# LPCB279_-_HBRIDGE.net
KiCad netlist of a schematic drawn in Altium Designer
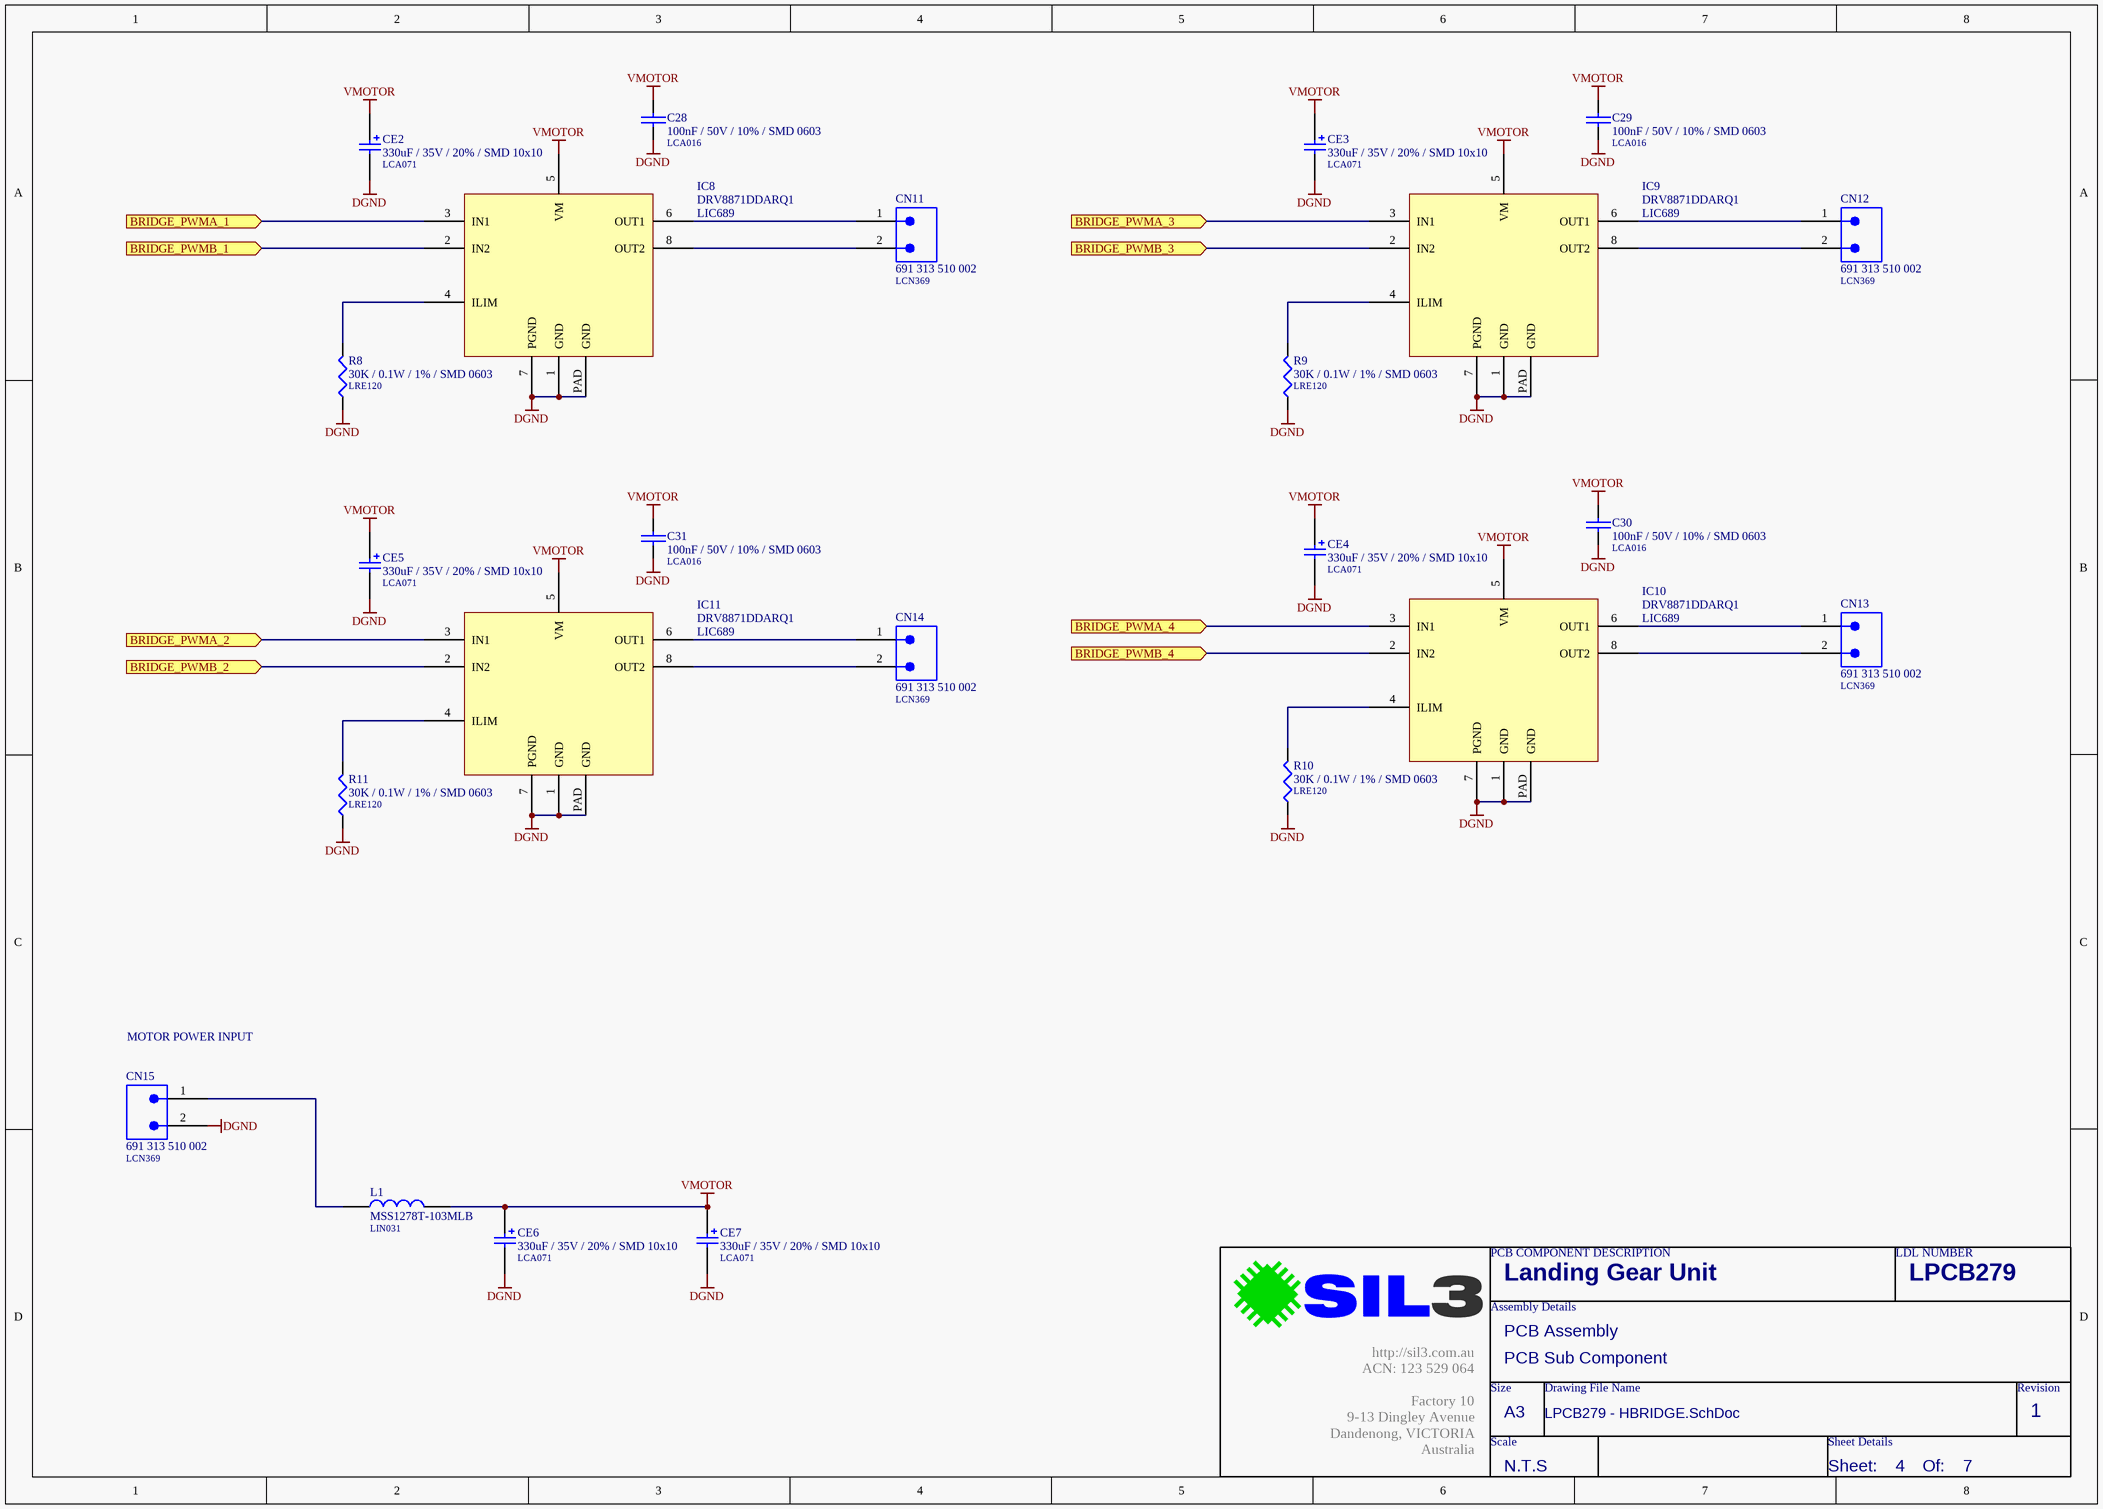
[diagram p0: LPCB279 - HBRIDGE.SchDoc]

(export (version "E")
  (design (tool "Eeschema 10.0.6"))
  (components
    (comp (ref "C28")
      (value "100nF / 50V / 10% / SMD 0603")
      (footprint "LFP011__CC1608-0603-IPC7351_B")
      (description "Capacitor, Ceramic Chip, 100nF (0.1uF), 50V, 5%, SMD 0603 [LCA016]")
      (fields (field (name "LDL_NUMBER") "LCA016"))
      (libsource (lib "LDL_Capacitors") (part "100nF / 50V / 10% / SMD 0603"))
    )
    (comp (ref "C29")
      (value "100nF / 50V / 10% / SMD 0603")
      (footprint "LFP011__CC1608-0603-IPC7351_B")
      (description "Capacitor, Ceramic Chip, 100nF (0.1uF), 50V, 5%, SMD 0603 [LCA016]")
      (fields (field (name "LDL_NUMBER") "LCA016"))
      (libsource (lib "LDL_Capacitors") (part "100nF / 50V / 10% / SMD 0603"))
    )
    (comp (ref "C30")
      (value "100nF / 50V / 10% / SMD 0603")
      (footprint "LFP011__CC1608-0603-IPC7351_B")
      (description "Capacitor, Ceramic Chip, 100nF (0.1uF), 50V, 5%, SMD 0603 [LCA016]")
      (fields (field (name "LDL_NUMBER") "LCA016"))
      (libsource (lib "LDL_Capacitors") (part "100nF / 50V / 10% / SMD 0603"))
    )
    (comp (ref "C31")
      (value "100nF / 50V / 10% / SMD 0603")
      (footprint "LFP011__CC1608-0603-IPC7351_B")
      (description "Capacitor, Ceramic Chip, 100nF (0.1uF), 50V, 5%, SMD 0603 [LCA016]")
      (fields (field (name "LDL_NUMBER") "LCA016"))
      (libsource (lib "LDL_Capacitors") (part "100nF / 50V / 10% / SMD 0603"))
    )
    (comp (ref "CE2")
      (value "330uF / 35V / 20% / SMD 10x10")
      (footprint "LFP041__NICHICON_WT_10X10")
      (description "Capacitor, Aluminum Electrolytic, 330uF, 35V, 20%, SMD (10mm x 10mm) [LCA071]")
      (fields (field (name "LDL_NUMBER") "LCA071"))
      (libsource (lib "LDL_Capacitors") (part "330uF / 35V / 20% / SMD 10x10"))
    )
    (comp (ref "CE3")
      (value "330uF / 35V / 20% / SMD 10x10")
      (footprint "LFP041__NICHICON_WT_10X10")
      (description "Capacitor, Aluminum Electrolytic, 330uF, 35V, 20%, SMD (10mm x 10mm) [LCA071]")
      (fields (field (name "LDL_NUMBER") "LCA071"))
      (libsource (lib "LDL_Capacitors") (part "330uF / 35V / 20% / SMD 10x10"))
    )
    (comp (ref "CE4")
      (value "330uF / 35V / 20% / SMD 10x10")
      (footprint "LFP041__NICHICON_WT_10X10")
      (description "Capacitor, Aluminum Electrolytic, 330uF, 35V, 20%, SMD (10mm x 10mm) [LCA071]")
      (fields (field (name "LDL_NUMBER") "LCA071"))
      (libsource (lib "LDL_Capacitors") (part "330uF / 35V / 20% / SMD 10x10"))
    )
    (comp (ref "CE5")
      (value "330uF / 35V / 20% / SMD 10x10")
      (footprint "LFP041__NICHICON_WT_10X10")
      (description "Capacitor, Aluminum Electrolytic, 330uF, 35V, 20%, SMD (10mm x 10mm) [LCA071]")
      (fields (field (name "LDL_NUMBER") "LCA071"))
      (libsource (lib "LDL_Capacitors") (part "330uF / 35V / 20% / SMD 10x10"))
    )
    (comp (ref "CE6")
      (value "330uF / 35V / 20% / SMD 10x10")
      (footprint "LFP041__NICHICON_WT_10X10")
      (description "Capacitor, Aluminum Electrolytic, 330uF, 35V, 20%, SMD (10mm x 10mm) [LCA071]")
      (fields (field (name "LDL_NUMBER") "LCA071"))
      (libsource (lib "LDL_Capacitors") (part "330uF / 35V / 20% / SMD 10x10"))
    )
    (comp (ref "CE7")
      (value "330uF / 35V / 20% / SMD 10x10")
      (footprint "LFP041__NICHICON_WT_10X10")
      (description "Capacitor, Aluminum Electrolytic, 330uF, 35V, 20%, SMD (10mm x 10mm) [LCA071]")
      (fields (field (name "LDL_NUMBER") "LCA071"))
      (libsource (lib "LDL_Capacitors") (part "330uF / 35V / 20% / SMD 10x10"))
    )
    (comp (ref "CN11")
      (value "691 313 510 002")
      (footprint "691 313 510 002")
      (description "Connector, Pluggable Terminal Block, 5.08mm, 2 Way, PTH")
      (fields (field (name "LDL_NUMBER") "LCN369"))
      (libsource (lib "LDL_Connectors") (part "691 313 510 002"))
    )
    (comp (ref "CN12")
      (value "691 313 510 002")
      (footprint "691 313 510 002")
      (description "Connector, Pluggable Terminal Block, 5.08mm, 2 Way, PTH")
      (fields (field (name "LDL_NUMBER") "LCN369"))
      (libsource (lib "LDL_Connectors") (part "691 313 510 002"))
    )
    (comp (ref "CN13")
      (value "691 313 510 002")
      (footprint "691 313 510 002")
      (description "Connector, Pluggable Terminal Block, 5.08mm, 2 Way, PTH")
      (fields (field (name "LDL_NUMBER") "LCN369"))
      (libsource (lib "LDL_Connectors") (part "691 313 510 002"))
    )
    (comp (ref "CN14")
      (value "691 313 510 002")
      (footprint "691 313 510 002")
      (description "Connector, Pluggable Terminal Block, 5.08mm, 2 Way, PTH")
      (fields (field (name "LDL_NUMBER") "LCN369"))
      (libsource (lib "LDL_Connectors") (part "691 313 510 002"))
    )
    (comp (ref "CN15")
      (value "691 313 510 002")
      (footprint "691 313 510 002")
      (description "Connector, Pluggable Terminal Block, 5.08mm, 2 Way, PTH")
      (fields (field (name "LDL_NUMBER") "LCN369"))
      (libsource (lib "LDL_Connectors") (part "691 313 510 002"))
    )
    (comp (ref "IC8")
      (value "DRV8871DDARQ1")
      (footprint "LFP158__DDA_R-PDSO-G8")
      (description "IC, DC Motor Driver, 3.6A, SMD [LIC689]")
      (fields (field (name "LDL_NUMBER") "LIC689"))
      (libsource (lib "LDL_Semiconductors") (part "DRV8871DDARQ1"))
    )
    (comp (ref "IC9")
      (value "DRV8871DDARQ1")
      (footprint "LFP158__DDA_R-PDSO-G8")
      (description "IC, DC Motor Driver, 3.6A, SMD [LIC689]")
      (fields (field (name "LDL_NUMBER") "LIC689"))
      (libsource (lib "LDL_Semiconductors") (part "DRV8871DDARQ1"))
    )
    (comp (ref "IC10")
      (value "DRV8871DDARQ1")
      (footprint "LFP158__DDA_R-PDSO-G8")
      (description "IC, DC Motor Driver, 3.6A, SMD [LIC689]")
      (fields (field (name "LDL_NUMBER") "LIC689"))
      (libsource (lib "LDL_Semiconductors") (part "DRV8871DDARQ1"))
    )
    (comp (ref "IC11")
      (value "DRV8871DDARQ1")
      (footprint "LFP158__DDA_R-PDSO-G8")
      (description "IC, DC Motor Driver, 3.6A, SMD [LIC689]")
      (fields (field (name "LDL_NUMBER") "LIC689"))
      (libsource (lib "LDL_Semiconductors") (part "DRV8871DDARQ1"))
    )
    (comp (ref "L1")
      (value "MSS1278T-103MLB")
      (footprint "LFP037__MSS1278T")
      (description "Inductor, 10uH, 20%, 5.7A, SMD [LIN031]")
      (fields (field (name "LDL_NUMBER") "LIN031"))
      (libsource (lib "LDL_Inductors") (part "MSS1278T-103MLB"))
    )
    (comp (ref "R8")
      (value "30K / 0.1W / 1% / SMD 0603")
      (footprint "LFP020__CR1608-0603-IPC7351_B")
      (description "Resistor, Ceramic Chip, 30K, 0.1W, 1%, SMD 0603 [LRE120]")
      (fields (field (name "LDL_NUMBER") "LRE120"))
      (libsource (lib "LDL_Resistors") (part "30K / 0.1W / 1% / SMD 0603"))
    )
    (comp (ref "R9")
      (value "30K / 0.1W / 1% / SMD 0603")
      (footprint "LFP020__CR1608-0603-IPC7351_B")
      (description "Resistor, Ceramic Chip, 30K, 0.1W, 1%, SMD 0603 [LRE120]")
      (fields (field (name "LDL_NUMBER") "LRE120"))
      (libsource (lib "LDL_Resistors") (part "30K / 0.1W / 1% / SMD 0603"))
    )
    (comp (ref "R10")
      (value "30K / 0.1W / 1% / SMD 0603")
      (footprint "LFP020__CR1608-0603-IPC7351_B")
      (description "Resistor, Ceramic Chip, 30K, 0.1W, 1%, SMD 0603 [LRE120]")
      (fields (field (name "LDL_NUMBER") "LRE120"))
      (libsource (lib "LDL_Resistors") (part "30K / 0.1W / 1% / SMD 0603"))
    )
    (comp (ref "R11")
      (value "30K / 0.1W / 1% / SMD 0603")
      (footprint "LFP020__CR1608-0603-IPC7351_B")
      (description "Resistor, Ceramic Chip, 30K, 0.1W, 1%, SMD 0603 [LRE120]")
      (fields (field (name "LDL_NUMBER") "LRE120"))
      (libsource (lib "LDL_Resistors") (part "30K / 0.1W / 1% / SMD 0603"))
    )
  )
  (nets
    (net (code "1") (name "/BRIDGE_PWMA_1") (class "Default")
      (node (ref "IC8") (pin "3") (pinfunction "IN1_3") (pintype "passive"))
    )
    (net (code "2") (name "/BRIDGE_PWMA_2") (class "Default")
      (node (ref "IC11") (pin "3") (pinfunction "IN1_3") (pintype "passive"))
    )
    (net (code "3") (name "/BRIDGE_PWMA_3") (class "Default")
      (node (ref "IC9") (pin "3") (pinfunction "IN1_3") (pintype "passive"))
    )
    (net (code "4") (name "/BRIDGE_PWMA_4") (class "Default")
      (node (ref "IC10") (pin "3") (pinfunction "IN1_3") (pintype "passive"))
    )
    (net (code "5") (name "/BRIDGE_PWMB_1") (class "Default")
      (node (ref "IC8") (pin "2") (pinfunction "IN2_2") (pintype "passive"))
    )
    (net (code "6") (name "/BRIDGE_PWMB_2") (class "Default")
      (node (ref "IC11") (pin "2") (pinfunction "IN2_2") (pintype "passive"))
    )
    (net (code "7") (name "/BRIDGE_PWMB_3") (class "Default")
      (node (ref "IC9") (pin "2") (pinfunction "IN2_2") (pintype "passive"))
    )
    (net (code "8") (name "/BRIDGE_PWMB_4") (class "Default")
      (node (ref "IC10") (pin "2") (pinfunction "IN2_2") (pintype "passive"))
    )
    (net (code "9") (name "DGND") (class "Default")
      (node (ref "C28") (pin "2") (pintype "passive"))
      (node (ref "C29") (pin "2") (pintype "passive"))
      (node (ref "C30") (pin "2") (pintype "passive"))
      (node (ref "C31") (pin "2") (pintype "passive"))
      (node (ref "CE2") (pin "2") (pinfunction "2_2") (pintype "passive"))
      (node (ref "CE3") (pin "2") (pinfunction "2_2") (pintype "passive"))
      (node (ref "CE4") (pin "2") (pinfunction "2_2") (pintype "passive"))
      (node (ref "CE5") (pin "2") (pinfunction "2_2") (pintype "passive"))
      (node (ref "CE6") (pin "2") (pinfunction "2_2") (pintype "passive"))
      (node (ref "CE7") (pin "2") (pinfunction "2_2") (pintype "passive"))
      (node (ref "CN15") (pin "2") (pinfunction "2_2") (pintype "passive"))
      (node (ref "IC10") (pin "1") (pinfunction "GND_1") (pintype "passive"))
      (node (ref "IC10") (pin "7") (pinfunction "PGND_7") (pintype "passive"))
      (node (ref "IC10") (pin "PAD") (pinfunction "GND_PAD") (pintype "passive"))
      (node (ref "IC11") (pin "1") (pinfunction "GND_1") (pintype "passive"))
      (node (ref "IC11") (pin "7") (pinfunction "PGND_7") (pintype "passive"))
      (node (ref "IC11") (pin "PAD") (pinfunction "GND_PAD") (pintype "passive"))
      (node (ref "IC8") (pin "1") (pinfunction "GND_1") (pintype "passive"))
      (node (ref "IC8") (pin "7") (pinfunction "PGND_7") (pintype "passive"))
      (node (ref "IC8") (pin "PAD") (pinfunction "GND_PAD") (pintype "passive"))
      (node (ref "IC9") (pin "1") (pinfunction "GND_1") (pintype "passive"))
      (node (ref "IC9") (pin "7") (pinfunction "PGND_7") (pintype "passive"))
      (node (ref "IC9") (pin "PAD") (pinfunction "GND_PAD") (pintype "passive"))
      (node (ref "R10") (pin "1") (pintype "passive"))
      (node (ref "R11") (pin "1") (pintype "passive"))
      (node (ref "R8") (pin "1") (pintype "passive"))
      (node (ref "R9") (pin "1") (pintype "passive"))
    )
    (net (code "10") (name "Net-(CN15-Pad1)") (class "Default")
      (node (ref "CN15") (pin "1") (pinfunction "1_1") (pintype "passive"))
      (node (ref "L1") (pin "1") (pinfunction "1_1") (pintype "passive"))
    )
    (net (code "11") (name "Net-(IC8-ILIM)") (class "Default")
      (node (ref "IC8") (pin "4") (pinfunction "ILIM_4") (pintype "passive"))
      (node (ref "R8") (pin "2") (pintype "passive"))
    )
    (net (code "12") (name "Net-(IC8-OUT1)") (class "Default")
      (node (ref "CN11") (pin "1") (pinfunction "1_1") (pintype "passive"))
      (node (ref "IC8") (pin "6") (pinfunction "OUT1_6") (pintype "passive"))
    )
    (net (code "13") (name "Net-(IC8-OUT2)") (class "Default")
      (node (ref "CN11") (pin "2") (pinfunction "2_2") (pintype "passive"))
      (node (ref "IC8") (pin "8") (pinfunction "OUT2_8") (pintype "passive"))
    )
    (net (code "14") (name "Net-(IC9-ILIM)") (class "Default")
      (node (ref "IC9") (pin "4") (pinfunction "ILIM_4") (pintype "passive"))
      (node (ref "R9") (pin "2") (pintype "passive"))
    )
    (net (code "15") (name "Net-(IC9-OUT1)") (class "Default")
      (node (ref "CN12") (pin "1") (pinfunction "1_1") (pintype "passive"))
      (node (ref "IC9") (pin "6") (pinfunction "OUT1_6") (pintype "passive"))
    )
    (net (code "16") (name "Net-(IC9-OUT2)") (class "Default")
      (node (ref "CN12") (pin "2") (pinfunction "2_2") (pintype "passive"))
      (node (ref "IC9") (pin "8") (pinfunction "OUT2_8") (pintype "passive"))
    )
    (net (code "17") (name "Net-(IC10-ILIM)") (class "Default")
      (node (ref "IC10") (pin "4") (pinfunction "ILIM_4") (pintype "passive"))
      (node (ref "R10") (pin "2") (pintype "passive"))
    )
    (net (code "18") (name "Net-(IC10-OUT1)") (class "Default")
      (node (ref "CN13") (pin "1") (pinfunction "1_1") (pintype "passive"))
      (node (ref "IC10") (pin "6") (pinfunction "OUT1_6") (pintype "passive"))
    )
    (net (code "19") (name "Net-(IC10-OUT2)") (class "Default")
      (node (ref "CN13") (pin "2") (pinfunction "2_2") (pintype "passive"))
      (node (ref "IC10") (pin "8") (pinfunction "OUT2_8") (pintype "passive"))
    )
    (net (code "20") (name "Net-(IC11-ILIM)") (class "Default")
      (node (ref "IC11") (pin "4") (pinfunction "ILIM_4") (pintype "passive"))
      (node (ref "R11") (pin "2") (pintype "passive"))
    )
    (net (code "21") (name "Net-(IC11-OUT1)") (class "Default")
      (node (ref "CN14") (pin "1") (pinfunction "1_1") (pintype "passive"))
      (node (ref "IC11") (pin "6") (pinfunction "OUT1_6") (pintype "passive"))
    )
    (net (code "22") (name "Net-(IC11-OUT2)") (class "Default")
      (node (ref "CN14") (pin "2") (pinfunction "2_2") (pintype "passive"))
      (node (ref "IC11") (pin "8") (pinfunction "OUT2_8") (pintype "passive"))
    )
    (net (code "23") (name "VMOTOR") (class "Default")
      (node (ref "C28") (pin "1") (pintype "passive"))
      (node (ref "C29") (pin "1") (pintype "passive"))
      (node (ref "C30") (pin "1") (pintype "passive"))
      (node (ref "C31") (pin "1") (pintype "passive"))
      (node (ref "CE2") (pin "1") (pinfunction "1_1") (pintype "passive"))
      (node (ref "CE3") (pin "1") (pinfunction "1_1") (pintype "passive"))
      (node (ref "CE4") (pin "1") (pinfunction "1_1") (pintype "passive"))
      (node (ref "CE5") (pin "1") (pinfunction "1_1") (pintype "passive"))
      (node (ref "CE6") (pin "1") (pinfunction "1_1") (pintype "passive"))
      (node (ref "CE7") (pin "1") (pinfunction "1_1") (pintype "passive"))
      (node (ref "IC10") (pin "5") (pinfunction "VM_5") (pintype "passive"))
      (node (ref "IC11") (pin "5") (pinfunction "VM_5") (pintype "passive"))
      (node (ref "IC8") (pin "5") (pinfunction "VM_5") (pintype "passive"))
      (node (ref "IC9") (pin "5") (pinfunction "VM_5") (pintype "passive"))
      (node (ref "L1") (pin "2") (pinfunction "2_2") (pintype "passive"))
    )
  )
)
